# oled_datalogger.net
KiCad netlist of a schematic drawn in EAGLE
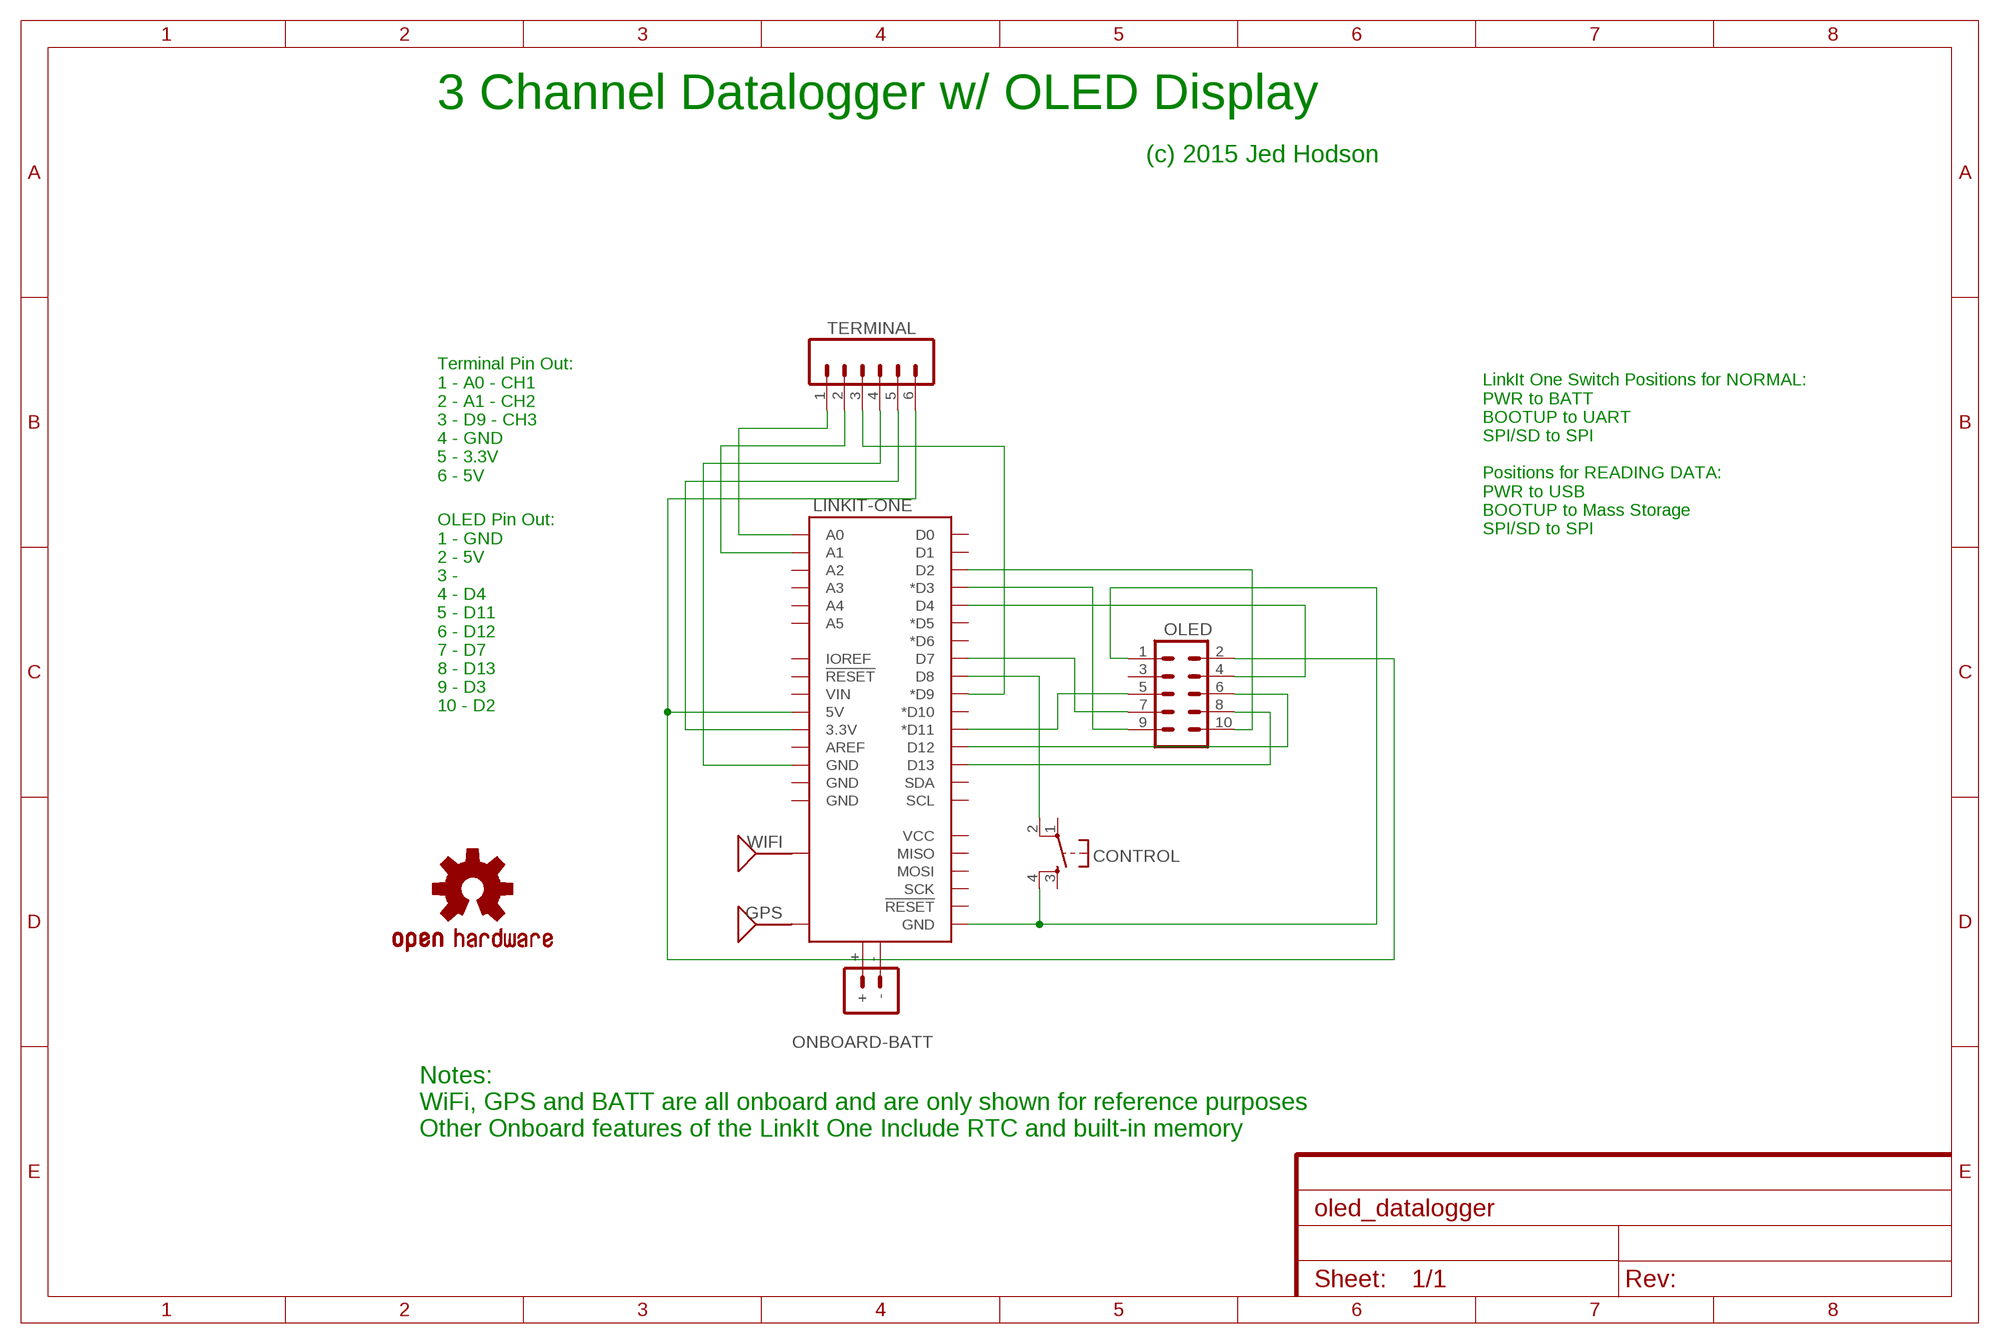
[diagram p0: schematic, sheet 1]

(export (version "E")
  (design (tool "Eeschema 10.0.6"))
  (components
    (comp (ref "CONTROL")
      (value "TAC_SWITCHPTH")
      (footprint "eagle-import:TACTILE-PTH")
      (libsource (lib "eagle-import") (part "TAC_SWITCHPTH"))
    )
    (comp (ref "GPS")
      (value "ANTENNA2SMD")
      (footprint "eagle-import:ANTENNA-CHIP2")
      (libsource (lib "eagle-import") (part "ANTENNA2SMD"))
    )
    (comp (ref "LINKIT-ONE")
      (value "ARDUINO_R3NO_HOLES")
      (footprint "eagle-import:ARDUINO_R3_NO_HOLES")
      (libsource (lib "eagle-import") (part "ARDUINO_R3NO_HOLES"))
    )
    (comp (ref "LOGO1")
      (value "OSHW-LOGOL")
      (footprint "eagle-import:OSHW-LOGO-L")
      (libsource (lib "eagle-import") (part "OSHW-LOGOL"))
    )
    (comp (ref "OLED")
      (value "M05X2NO_SILK")
      (footprint "eagle-import:2X5_NOSILK")
      (libsource (lib "eagle-import") (part "M05X2NO_SILK"))
    )
    (comp (ref "ONBOARD-BATT")
      (value "BATTERY_CONNDEANS")
      (footprint "eagle-import:DEANS")
      (libsource (lib "eagle-import") (part "BATTERY_CONNDEANS"))
    )
    (comp (ref "TERMINAL")
      (value "M06POGOPIN_HOLES_ONLY")
      (footprint "eagle-import:1X06_HOLES_ONLY")
      (libsource (lib "eagle-import") (part "M06POGOPIN_HOLES_ONLY"))
    )
    (comp (ref "WIFI")
      (value "ANTENNA2SMD")
      (footprint "eagle-import:ANTENNA-CHIP2")
      (libsource (lib "eagle-import") (part "ANTENNA2SMD"))
    )
  )
  (nets
    (net (code "1") (name "Net-(CONTROL-Pad2)") (class "Default")
      (node (ref "CONTROL") (pin "2") (pinfunction "2_2") (pintype "passive"))
      (node (ref "LINKIT-ONE") (pin "D8") (pinfunction "D8_D8") (pintype "bidirectional"))
    )
    (net (code "2") (name "Net-(CONTROL-Pad4)") (class "Default")
      (node (ref "CONTROL") (pin "4") (pinfunction "4_4") (pintype "passive"))
      (node (ref "LINKIT-ONE") (pin "GND@1") (pinfunction "GND_GND@1") (pintype "bidirectional"))
      (node (ref "OLED") (pin "1") (pinfunction "1_1") (pintype "passive"))
    )
    (net (code "3") (name "Net-(LINKIT-ONE-*D3)") (class "Default")
      (node (ref "LINKIT-ONE") (pin "D3") (pinfunction "*D3_D3") (pintype "bidirectional"))
      (node (ref "OLED") (pin "9") (pinfunction "9_9") (pintype "passive"))
    )
    (net (code "4") (name "Net-(LINKIT-ONE-*D9)") (class "Default")
      (node (ref "LINKIT-ONE") (pin "D9") (pinfunction "*D9_D9") (pintype "bidirectional"))
      (node (ref "TERMINAL") (pin "3") (pinfunction "3_3") (pintype "passive"))
    )
    (net (code "5") (name "Net-(LINKIT-ONE-*D11)") (class "Default")
      (node (ref "LINKIT-ONE") (pin "D11") (pinfunction "*D11_D11") (pintype "bidirectional"))
      (node (ref "OLED") (pin "5") (pinfunction "5_5") (pintype "passive"))
    )
    (net (code "6") (name "Net-(LINKIT-ONE-GND-PadGND@4)") (class "Default")
      (node (ref "LINKIT-ONE") (pin "GND@4") (pinfunction "GND_GND@4") (pintype "bidirectional"))
      (node (ref "TERMINAL") (pin "4") (pinfunction "4_4") (pintype "passive"))
    )
    (net (code "7") (name "Net-(LINKIT-ONE-Pad3.3V)") (class "Default")
      (node (ref "LINKIT-ONE") (pin "3.3V") (pinfunction "3.3V_3.3V") (pintype "bidirectional"))
      (node (ref "TERMINAL") (pin "5") (pinfunction "5_5") (pintype "passive"))
    )
    (net (code "8") (name "Net-(LINKIT-ONE-Pad5V)") (class "Default")
      (node (ref "LINKIT-ONE") (pin "5V") (pinfunction "5V_5V") (pintype "bidirectional"))
      (node (ref "OLED") (pin "2") (pinfunction "2_2") (pintype "passive"))
      (node (ref "TERMINAL") (pin "6") (pinfunction "6_6") (pintype "passive"))
    )
    (net (code "9") (name "Net-(LINKIT-ONE-PadA0)") (class "Default")
      (node (ref "LINKIT-ONE") (pin "A0") (pinfunction "A0_A0") (pintype "bidirectional"))
      (node (ref "TERMINAL") (pin "1") (pinfunction "1_1") (pintype "passive"))
    )
    (net (code "10") (name "Net-(LINKIT-ONE-PadA1)") (class "Default")
      (node (ref "LINKIT-ONE") (pin "A1") (pinfunction "A1_A1") (pintype "bidirectional"))
      (node (ref "TERMINAL") (pin "2") (pinfunction "2_2") (pintype "passive"))
    )
    (net (code "11") (name "Net-(LINKIT-ONE-PadD2)") (class "Default")
      (node (ref "LINKIT-ONE") (pin "D2") (pinfunction "D2_D2") (pintype "bidirectional"))
      (node (ref "OLED") (pin "10") (pinfunction "10_10") (pintype "passive"))
    )
    (net (code "12") (name "Net-(LINKIT-ONE-PadD4)") (class "Default")
      (node (ref "LINKIT-ONE") (pin "D4") (pinfunction "D4_D4") (pintype "bidirectional"))
      (node (ref "OLED") (pin "4") (pinfunction "4_4") (pintype "passive"))
    )
    (net (code "13") (name "Net-(LINKIT-ONE-PadD7)") (class "Default")
      (node (ref "LINKIT-ONE") (pin "D7") (pinfunction "D7_D7") (pintype "bidirectional"))
      (node (ref "OLED") (pin "7") (pinfunction "7_7") (pintype "passive"))
    )
    (net (code "14") (name "Net-(LINKIT-ONE-PadD12)") (class "Default")
      (node (ref "LINKIT-ONE") (pin "D12") (pinfunction "D12_D12") (pintype "bidirectional"))
      (node (ref "OLED") (pin "6") (pinfunction "6_6") (pintype "passive"))
    )
    (net (code "15") (name "Net-(LINKIT-ONE-PadD13)") (class "Default")
      (node (ref "LINKIT-ONE") (pin "D13") (pinfunction "D13_D13") (pintype "bidirectional"))
      (node (ref "OLED") (pin "8") (pinfunction "8_8") (pintype "passive"))
    )
    (net (code "16") (name "unconnected-(CONTROL-Pad1)") (class "Default")
      (node (ref "CONTROL") (pin "1") (pinfunction "1_1") (pintype "passive"))
    )
    (net (code "17") (name "unconnected-(CONTROL-Pad3)") (class "Default")
      (node (ref "CONTROL") (pin "3") (pinfunction "3_3") (pintype "passive"))
    )
    (net (code "18") (name "unconnected-(GPS-SIGNAL-PadFEED)") (class "Default")
      (node (ref "GPS") (pin "FEED") (pinfunction "SIGNAL_FEED") (pintype "bidirectional"))
    )
    (net (code "19") (name "unconnected-(LINKIT-ONE-*D5-PadD5)") (class "Default")
      (node (ref "LINKIT-ONE") (pin "D5") (pinfunction "*D5_D5") (pintype "bidirectional"))
    )
    (net (code "20") (name "unconnected-(LINKIT-ONE-*D6-PadD6)") (class "Default")
      (node (ref "LINKIT-ONE") (pin "D6") (pinfunction "*D6_D6") (pintype "bidirectional"))
    )
    (net (code "21") (name "unconnected-(LINKIT-ONE-*D10-PadD10)") (class "Default")
      (node (ref "LINKIT-ONE") (pin "D10") (pinfunction "*D10_D10") (pintype "bidirectional"))
    )
    (net (code "22") (name "unconnected-(LINKIT-ONE-GND-PadGND@2)") (class "Default")
      (node (ref "LINKIT-ONE") (pin "GND@2") (pinfunction "GND_GND@2") (pintype "bidirectional"))
    )
    (net (code "23") (name "unconnected-(LINKIT-ONE-GND-PadGND@3)") (class "Default")
      (node (ref "LINKIT-ONE") (pin "GND@3") (pinfunction "GND_GND@3") (pintype "bidirectional"))
    )
    (net (code "24") (name "unconnected-(LINKIT-ONE-PadA2)") (class "Default")
      (node (ref "LINKIT-ONE") (pin "A2") (pinfunction "A2_A2") (pintype "bidirectional"))
    )
    (net (code "25") (name "unconnected-(LINKIT-ONE-PadA3)") (class "Default")
      (node (ref "LINKIT-ONE") (pin "A3") (pinfunction "A3_A3") (pintype "bidirectional"))
    )
    (net (code "26") (name "unconnected-(LINKIT-ONE-PadA4)") (class "Default")
      (node (ref "LINKIT-ONE") (pin "A4") (pinfunction "A4_A4") (pintype "bidirectional"))
    )
    (net (code "27") (name "unconnected-(LINKIT-ONE-PadA5)") (class "Default")
      (node (ref "LINKIT-ONE") (pin "A5") (pinfunction "A5_A5") (pintype "bidirectional"))
    )
    (net (code "28") (name "unconnected-(LINKIT-ONE-PadAREF)") (class "Default")
      (node (ref "LINKIT-ONE") (pin "AREF") (pinfunction "AREF_AREF") (pintype "bidirectional"))
    )
    (net (code "29") (name "unconnected-(LINKIT-ONE-PadD0)") (class "Default")
      (node (ref "LINKIT-ONE") (pin "D0") (pinfunction "D0_D0") (pintype "bidirectional"))
    )
    (net (code "30") (name "unconnected-(LINKIT-ONE-PadD1)") (class "Default")
      (node (ref "LINKIT-ONE") (pin "D1") (pinfunction "D1_D1") (pintype "bidirectional"))
    )
    (net (code "31") (name "unconnected-(LINKIT-ONE-PadIOREF)") (class "Default")
      (node (ref "LINKIT-ONE") (pin "IOREF") (pinfunction "IOREF_IOREF") (pintype "bidirectional"))
    )
    (net (code "32") (name "unconnected-(LINKIT-ONE-PadMISO)") (class "Default")
      (node (ref "LINKIT-ONE") (pin "MISO") (pinfunction "MISO_MISO") (pintype "bidirectional"))
    )
    (net (code "33") (name "unconnected-(LINKIT-ONE-PadMOSI)") (class "Default")
      (node (ref "LINKIT-ONE") (pin "MOSI") (pinfunction "MOSI_MOSI") (pintype "bidirectional"))
    )
    (net (code "34") (name "unconnected-(LINKIT-ONE-PadSCK)") (class "Default")
      (node (ref "LINKIT-ONE") (pin "SCK") (pinfunction "SCK_SCK") (pintype "bidirectional"))
    )
    (net (code "35") (name "unconnected-(LINKIT-ONE-PadSCL)") (class "Default")
      (node (ref "LINKIT-ONE") (pin "SCL") (pinfunction "SCL_SCL") (pintype "bidirectional"))
    )
    (net (code "36") (name "unconnected-(LINKIT-ONE-PadSDA)") (class "Default")
      (node (ref "LINKIT-ONE") (pin "SDA") (pinfunction "SDA_SDA") (pintype "bidirectional"))
    )
    (net (code "37") (name "unconnected-(LINKIT-ONE-PadVCC)") (class "Default")
      (node (ref "LINKIT-ONE") (pin "VCC") (pinfunction "VCC_VCC") (pintype "bidirectional"))
    )
    (net (code "38") (name "unconnected-(LINKIT-ONE-PadVIN)") (class "Default")
      (node (ref "LINKIT-ONE") (pin "VIN") (pinfunction "VIN_VIN") (pintype "bidirectional"))
    )
    (net (code "39") (name "unconnected-(LINKIT-ONE-~{RESET}-PadRESET@1)") (class "Default")
      (node (ref "LINKIT-ONE") (pin "RESET@1") (pinfunction "~{RESET}_RESET@1") (pintype "bidirectional"))
    )
    (net (code "40") (name "unconnected-(LINKIT-ONE-~{RESET}-PadRESET@2)") (class "Default")
      (node (ref "LINKIT-ONE") (pin "RESET@2") (pinfunction "~{RESET}_RESET@2") (pintype "bidirectional"))
    )
    (net (code "41") (name "unconnected-(OLED-Pad3)") (class "Default")
      (node (ref "OLED") (pin "3") (pinfunction "3_3") (pintype "passive"))
    )
    (net (code "42") (name "unconnected-(ONBOARD-BATT-Pad+)") (class "Default")
      (node (ref "ONBOARD-BATT") (pin "+") (pinfunction "+_+") (pintype "passive"))
    )
    (net (code "43") (name "unconnected-(ONBOARD-BATT-Pad-)") (class "Default")
      (node (ref "ONBOARD-BATT") (pin "-") (pinfunction "-_-") (pintype "passive"))
    )
    (net (code "44") (name "unconnected-(WIFI-SIGNAL-PadFEED)") (class "Default")
      (node (ref "WIFI") (pin "FEED") (pinfunction "SIGNAL_FEED") (pintype "bidirectional"))
    )
  )
)
